# qube.net
KiCad netlist of a schematic drawn in EAGLE
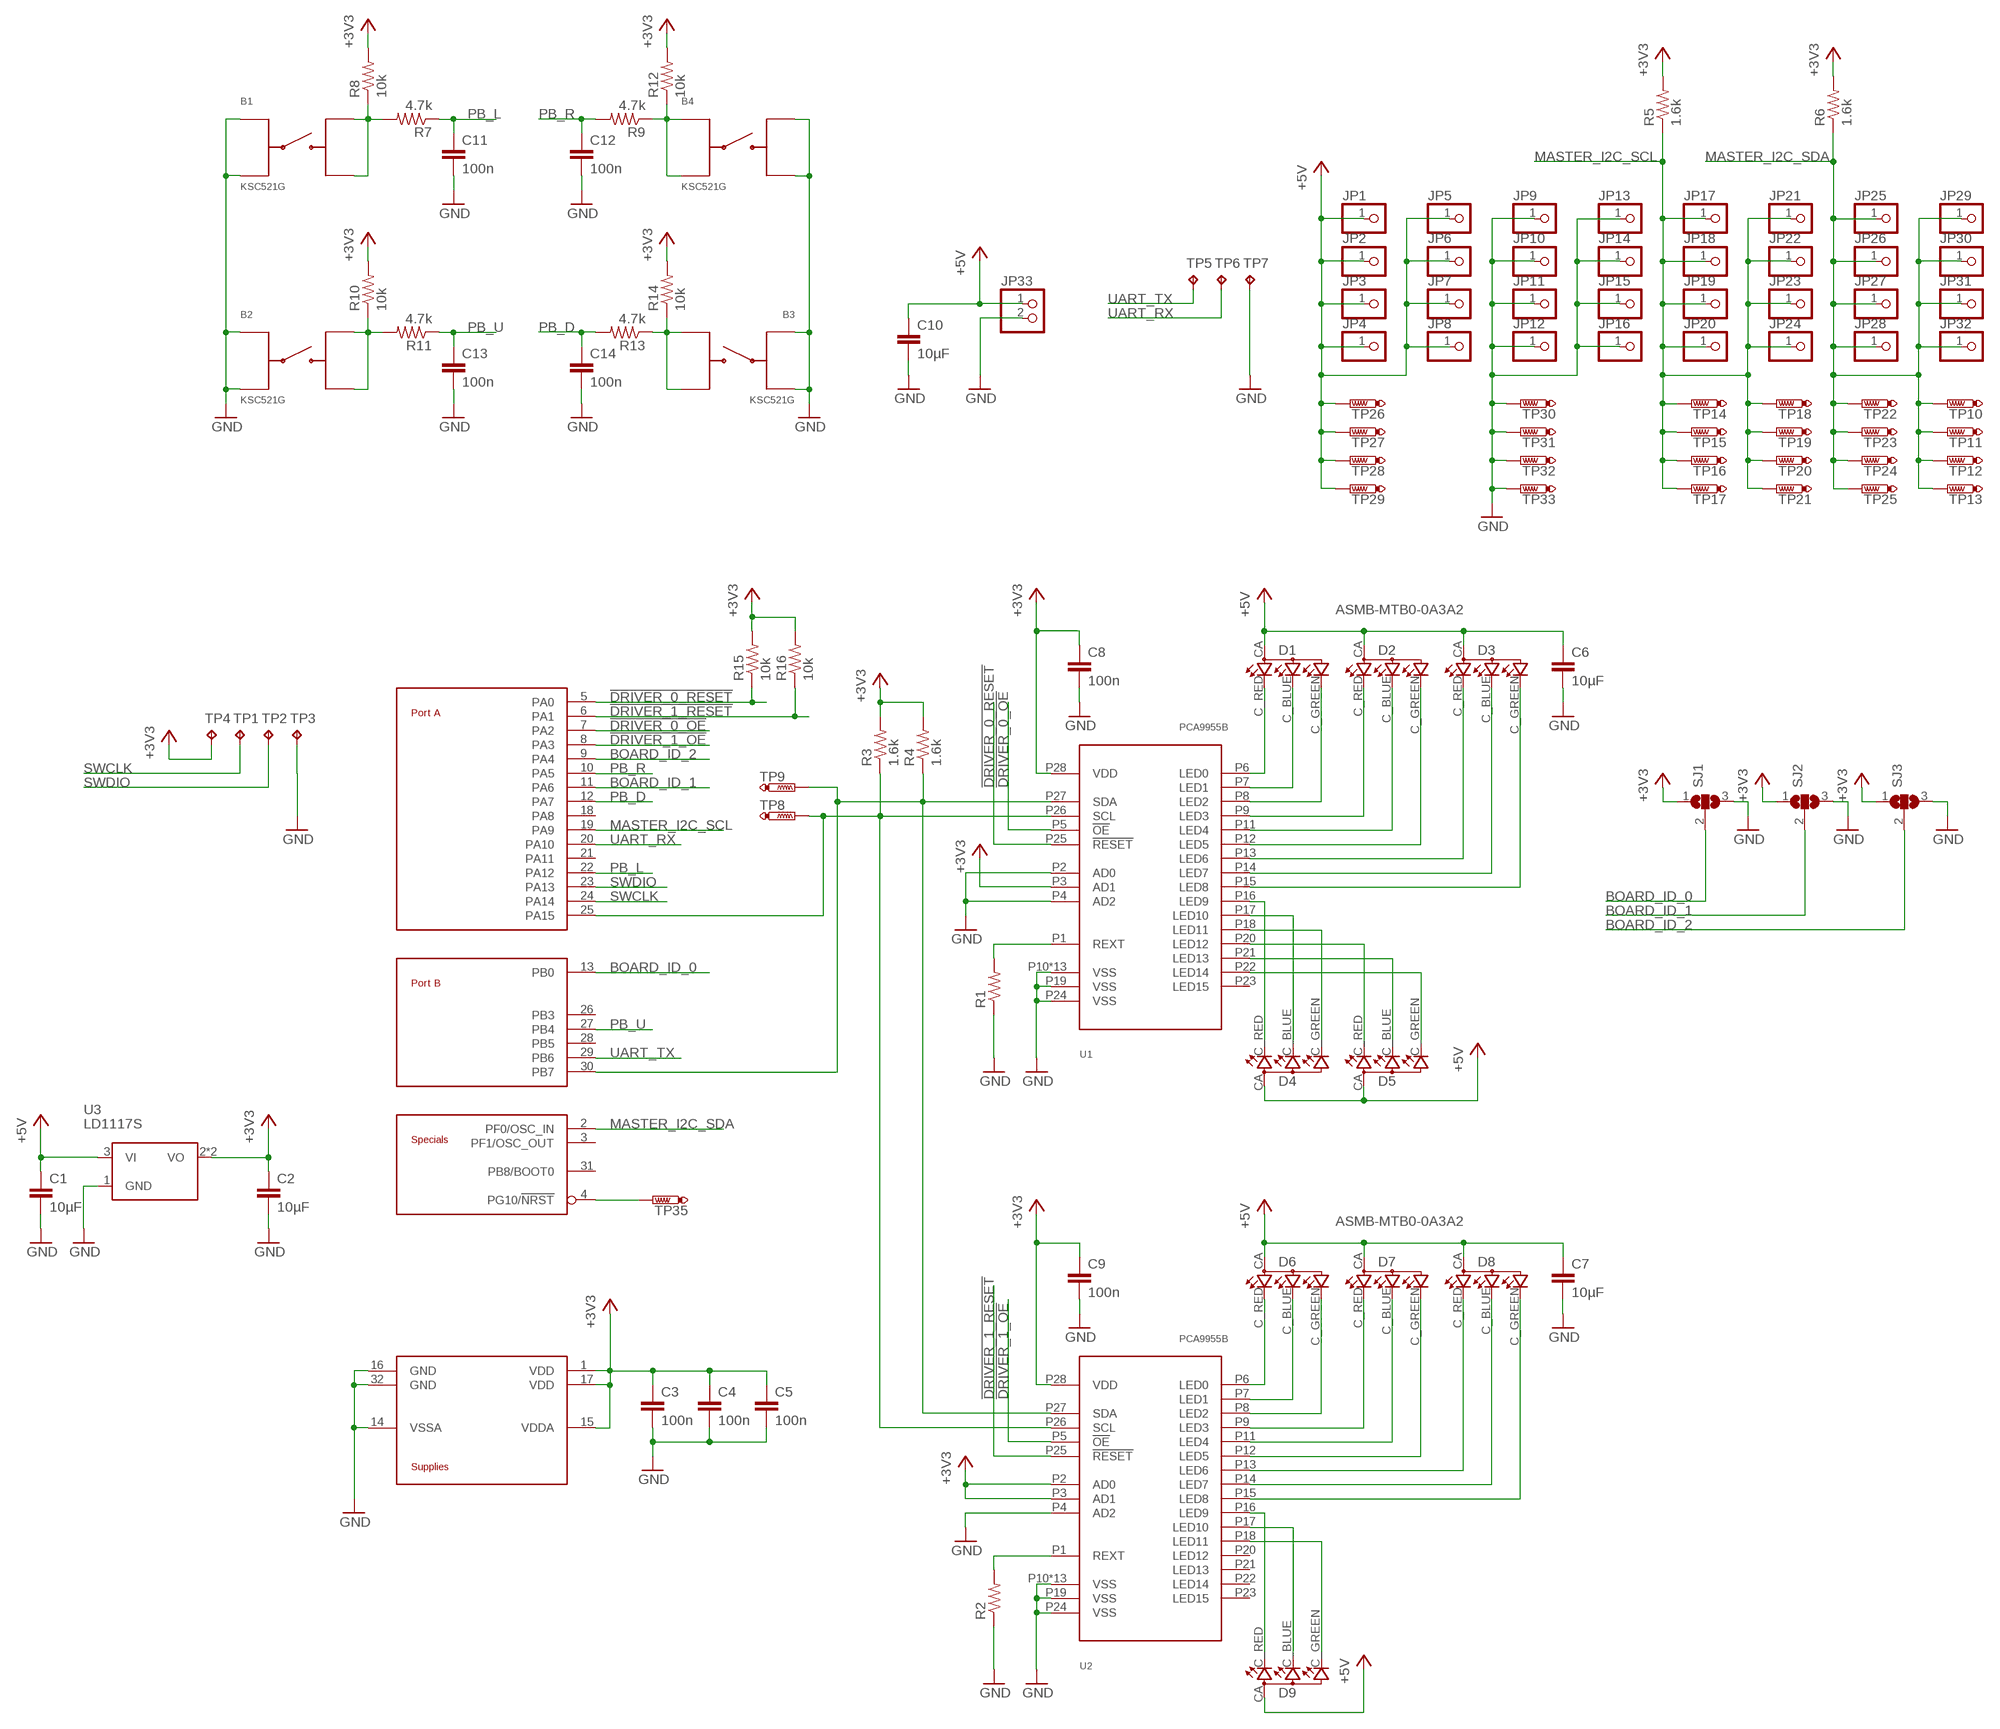
[diagram p0: schematic, sheet 1]

(export (version "E")
  (design (tool "Eeschema 10.0.6"))
  (components
    (comp (ref "B1")
      (value "KSC521G")
      (footprint "eagle-import:KSC521G")
      (libsource (lib "eagle-import") (part "KSC521G"))
    )
    (comp (ref "B2")
      (value "KSC521G")
      (footprint "eagle-import:KSC521G")
      (libsource (lib "eagle-import") (part "KSC521G"))
    )
    (comp (ref "B3")
      (value "KSC521G")
      (footprint "eagle-import:KSC521G")
      (libsource (lib "eagle-import") (part "KSC521G"))
    )
    (comp (ref "B4")
      (value "KSC521G")
      (footprint "eagle-import:KSC521G")
      (libsource (lib "eagle-import") (part "KSC521G"))
    )
    (comp (ref "C1")
      (value "10µF")
      (footprint "eagle-import:C0805")
      (libsource (lib "eagle-import") (part "C-EUC0805"))
    )
    (comp (ref "C2")
      (value "10µF")
      (footprint "eagle-import:C0805")
      (libsource (lib "eagle-import") (part "C-EUC0805"))
    )
    (comp (ref "C3")
      (value "100n")
      (footprint "eagle-import:C0805")
      (libsource (lib "eagle-import") (part "C-EUC0805"))
    )
    (comp (ref "C4")
      (value "100n")
      (footprint "eagle-import:C0805")
      (libsource (lib "eagle-import") (part "C-EUC0805"))
    )
    (comp (ref "C5")
      (value "100n")
      (footprint "eagle-import:C0805")
      (libsource (lib "eagle-import") (part "C-EUC0805"))
    )
    (comp (ref "C6")
      (value "10µF")
      (footprint "eagle-import:C0805")
      (libsource (lib "eagle-import") (part "C-EUC0805"))
    )
    (comp (ref "C7")
      (value "10µF")
      (footprint "eagle-import:C0805")
      (libsource (lib "eagle-import") (part "C-EUC0805"))
    )
    (comp (ref "C8")
      (value "100n")
      (footprint "eagle-import:C0805")
      (libsource (lib "eagle-import") (part "C-EUC0805"))
    )
    (comp (ref "C9")
      (value "100n")
      (footprint "eagle-import:C0805")
      (libsource (lib "eagle-import") (part "C-EUC0805"))
    )
    (comp (ref "C10")
      (value "10µF")
      (footprint "eagle-import:C0805")
      (libsource (lib "eagle-import") (part "C-EUC0805"))
    )
    (comp (ref "C11")
      (value "100n")
      (footprint "eagle-import:C0805")
      (libsource (lib "eagle-import") (part "C-EUC0805"))
    )
    (comp (ref "C12")
      (value "100n")
      (footprint "eagle-import:C0805")
      (libsource (lib "eagle-import") (part "C-EUC0805"))
    )
    (comp (ref "C13")
      (value "100n")
      (footprint "eagle-import:C0805")
      (libsource (lib "eagle-import") (part "C-EUC0805"))
    )
    (comp (ref "C14")
      (value "100n")
      (footprint "eagle-import:C0805")
      (libsource (lib "eagle-import") (part "C-EUC0805"))
    )
    (comp (ref "D1")
      (value "ASMB-MTB0-0A3A2")
      (footprint "eagle-import:PLCC-4")
      (libsource (lib "eagle-import") (part "ASMB-MTB0-0A3A2"))
    )
    (comp (ref "D2")
      (value "ASMB-MTB0-0A3A2")
      (footprint "eagle-import:PLCC-4")
      (libsource (lib "eagle-import") (part "ASMB-MTB0-0A3A2"))
    )
    (comp (ref "D3")
      (value "ASMB-MTB0-0A3A2")
      (footprint "eagle-import:PLCC-4")
      (libsource (lib "eagle-import") (part "ASMB-MTB0-0A3A2"))
    )
    (comp (ref "D4")
      (value "ASMB-MTB0-0A3A2")
      (footprint "eagle-import:PLCC-4")
      (libsource (lib "eagle-import") (part "ASMB-MTB0-0A3A2"))
    )
    (comp (ref "D5")
      (value "ASMB-MTB0-0A3A2")
      (footprint "eagle-import:PLCC-4")
      (libsource (lib "eagle-import") (part "ASMB-MTB0-0A3A2"))
    )
    (comp (ref "D6")
      (value "ASMB-MTB0-0A3A2")
      (footprint "eagle-import:PLCC-4")
      (libsource (lib "eagle-import") (part "ASMB-MTB0-0A3A2"))
    )
    (comp (ref "D7")
      (value "ASMB-MTB0-0A3A2")
      (footprint "eagle-import:PLCC-4")
      (libsource (lib "eagle-import") (part "ASMB-MTB0-0A3A2"))
    )
    (comp (ref "D8")
      (value "ASMB-MTB0-0A3A2")
      (footprint "eagle-import:PLCC-4")
      (libsource (lib "eagle-import") (part "ASMB-MTB0-0A3A2"))
    )
    (comp (ref "D9")
      (value "ASMB-MTB0-0A3A2")
      (footprint "eagle-import:PLCC-4")
      (libsource (lib "eagle-import") (part "ASMB-MTB0-0A3A2"))
    )
    (comp (ref "JP1")
      (value "PINHD-1X1")
      (footprint "eagle-import:1X01")
      (libsource (lib "eagle-import") (part "PINHD-1X1"))
    )
    (comp (ref "JP2")
      (value "PINHD-1X1")
      (footprint "eagle-import:1X01")
      (libsource (lib "eagle-import") (part "PINHD-1X1"))
    )
    (comp (ref "JP3")
      (value "PINHD-1X1")
      (footprint "eagle-import:1X01")
      (libsource (lib "eagle-import") (part "PINHD-1X1"))
    )
    (comp (ref "JP4")
      (value "PINHD-1X1")
      (footprint "eagle-import:1X01")
      (libsource (lib "eagle-import") (part "PINHD-1X1"))
    )
    (comp (ref "JP5")
      (value "PINHD-1X1")
      (footprint "eagle-import:1X01")
      (libsource (lib "eagle-import") (part "PINHD-1X1"))
    )
    (comp (ref "JP6")
      (value "PINHD-1X1")
      (footprint "eagle-import:1X01")
      (libsource (lib "eagle-import") (part "PINHD-1X1"))
    )
    (comp (ref "JP7")
      (value "PINHD-1X1")
      (footprint "eagle-import:1X01")
      (libsource (lib "eagle-import") (part "PINHD-1X1"))
    )
    (comp (ref "JP8")
      (value "PINHD-1X1")
      (footprint "eagle-import:1X01")
      (libsource (lib "eagle-import") (part "PINHD-1X1"))
    )
    (comp (ref "JP9")
      (value "PINHD-1X1")
      (footprint "eagle-import:1X01")
      (libsource (lib "eagle-import") (part "PINHD-1X1"))
    )
    (comp (ref "JP10")
      (value "PINHD-1X1")
      (footprint "eagle-import:1X01")
      (libsource (lib "eagle-import") (part "PINHD-1X1"))
    )
    (comp (ref "JP11")
      (value "PINHD-1X1")
      (footprint "eagle-import:1X01")
      (libsource (lib "eagle-import") (part "PINHD-1X1"))
    )
    (comp (ref "JP12")
      (value "PINHD-1X1")
      (footprint "eagle-import:1X01")
      (libsource (lib "eagle-import") (part "PINHD-1X1"))
    )
    (comp (ref "JP13")
      (value "PINHD-1X1")
      (footprint "eagle-import:1X01")
      (libsource (lib "eagle-import") (part "PINHD-1X1"))
    )
    (comp (ref "JP14")
      (value "PINHD-1X1")
      (footprint "eagle-import:1X01")
      (libsource (lib "eagle-import") (part "PINHD-1X1"))
    )
    (comp (ref "JP15")
      (value "PINHD-1X1")
      (footprint "eagle-import:1X01")
      (libsource (lib "eagle-import") (part "PINHD-1X1"))
    )
    (comp (ref "JP16")
      (value "PINHD-1X1")
      (footprint "eagle-import:1X01")
      (libsource (lib "eagle-import") (part "PINHD-1X1"))
    )
    (comp (ref "JP17")
      (value "PINHD-1X1")
      (footprint "eagle-import:1X01")
      (libsource (lib "eagle-import") (part "PINHD-1X1"))
    )
    (comp (ref "JP18")
      (value "PINHD-1X1")
      (footprint "eagle-import:1X01")
      (libsource (lib "eagle-import") (part "PINHD-1X1"))
    )
    (comp (ref "JP19")
      (value "PINHD-1X1")
      (footprint "eagle-import:1X01")
      (libsource (lib "eagle-import") (part "PINHD-1X1"))
    )
    (comp (ref "JP20")
      (value "PINHD-1X1")
      (footprint "eagle-import:1X01")
      (libsource (lib "eagle-import") (part "PINHD-1X1"))
    )
    (comp (ref "JP21")
      (value "PINHD-1X1")
      (footprint "eagle-import:1X01")
      (libsource (lib "eagle-import") (part "PINHD-1X1"))
    )
    (comp (ref "JP22")
      (value "PINHD-1X1")
      (footprint "eagle-import:1X01")
      (libsource (lib "eagle-import") (part "PINHD-1X1"))
    )
    (comp (ref "JP23")
      (value "PINHD-1X1")
      (footprint "eagle-import:1X01")
      (libsource (lib "eagle-import") (part "PINHD-1X1"))
    )
    (comp (ref "JP24")
      (value "PINHD-1X1")
      (footprint "eagle-import:1X01")
      (libsource (lib "eagle-import") (part "PINHD-1X1"))
    )
    (comp (ref "JP25")
      (value "PINHD-1X1")
      (footprint "eagle-import:1X01")
      (libsource (lib "eagle-import") (part "PINHD-1X1"))
    )
    (comp (ref "JP26")
      (value "PINHD-1X1")
      (footprint "eagle-import:1X01")
      (libsource (lib "eagle-import") (part "PINHD-1X1"))
    )
    (comp (ref "JP27")
      (value "PINHD-1X1")
      (footprint "eagle-import:1X01")
      (libsource (lib "eagle-import") (part "PINHD-1X1"))
    )
    (comp (ref "JP28")
      (value "PINHD-1X1")
      (footprint "eagle-import:1X01")
      (libsource (lib "eagle-import") (part "PINHD-1X1"))
    )
    (comp (ref "JP29")
      (value "PINHD-1X1")
      (footprint "eagle-import:1X01")
      (libsource (lib "eagle-import") (part "PINHD-1X1"))
    )
    (comp (ref "JP30")
      (value "PINHD-1X1")
      (footprint "eagle-import:1X01")
      (libsource (lib "eagle-import") (part "PINHD-1X1"))
    )
    (comp (ref "JP31")
      (value "PINHD-1X1")
      (footprint "eagle-import:1X01")
      (libsource (lib "eagle-import") (part "PINHD-1X1"))
    )
    (comp (ref "JP32")
      (value "PINHD-1X1")
      (footprint "eagle-import:1X01")
      (libsource (lib "eagle-import") (part "PINHD-1X1"))
    )
    (comp (ref "JP33")
      (value "PINHD-1X2/90")
      (footprint "eagle-import:1X02_90")
      (libsource (lib "eagle-import") (part "PINHD-1X2/90"))
    )
    (comp (ref "R1")
      (value "R-US_R0805")
      (footprint "eagle-import:R0805")
      (libsource (lib "eagle-import") (part "R-US_R0805"))
    )
    (comp (ref "R2")
      (value "R-US_R0805")
      (footprint "eagle-import:R0805")
      (libsource (lib "eagle-import") (part "R-US_R0805"))
    )
    (comp (ref "R3")
      (value "1.6k")
      (footprint "eagle-import:R0805")
      (libsource (lib "eagle-import") (part "R-US_R0805"))
    )
    (comp (ref "R4")
      (value "1.6k")
      (footprint "eagle-import:R0805")
      (libsource (lib "eagle-import") (part "R-US_R0805"))
    )
    (comp (ref "R5")
      (value "1.6k")
      (footprint "eagle-import:R0805")
      (libsource (lib "eagle-import") (part "R-US_R0805"))
    )
    (comp (ref "R6")
      (value "1.6k")
      (footprint "eagle-import:R0805")
      (libsource (lib "eagle-import") (part "R-US_R0805"))
    )
    (comp (ref "R7")
      (value "4.7k")
      (footprint "eagle-import:R0805")
      (libsource (lib "eagle-import") (part "R-US_R0805"))
    )
    (comp (ref "R8")
      (value "10k")
      (footprint "eagle-import:R0805")
      (libsource (lib "eagle-import") (part "R-US_R0805"))
    )
    (comp (ref "R9")
      (value "4.7k")
      (footprint "eagle-import:R0805")
      (libsource (lib "eagle-import") (part "R-US_R0805"))
    )
    (comp (ref "R10")
      (value "10k")
      (footprint "eagle-import:R0805")
      (libsource (lib "eagle-import") (part "R-US_R0805"))
    )
    (comp (ref "R11")
      (value "4.7k")
      (footprint "eagle-import:R0805")
      (libsource (lib "eagle-import") (part "R-US_R0805"))
    )
    (comp (ref "R12")
      (value "10k")
      (footprint "eagle-import:R0805")
      (libsource (lib "eagle-import") (part "R-US_R0805"))
    )
    (comp (ref "R13")
      (value "4.7k")
      (footprint "eagle-import:R0805")
      (libsource (lib "eagle-import") (part "R-US_R0805"))
    )
    (comp (ref "R14")
      (value "10k")
      (footprint "eagle-import:R0805")
      (libsource (lib "eagle-import") (part "R-US_R0805"))
    )
    (comp (ref "R15")
      (value "10k")
      (footprint "eagle-import:R0805")
      (libsource (lib "eagle-import") (part "R-US_R0805"))
    )
    (comp (ref "R16")
      (value "10k")
      (footprint "eagle-import:R0805")
      (libsource (lib "eagle-import") (part "R-US_R0805"))
    )
    (comp (ref "SJ1")
      (value "SJ2W")
      (footprint "eagle-import:SJ_2")
      (libsource (lib "eagle-import") (part "SJ2W"))
    )
    (comp (ref "SJ2")
      (value "SJ2W")
      (footprint "eagle-import:SJ_2")
      (libsource (lib "eagle-import") (part "SJ2W"))
    )
    (comp (ref "SJ3")
      (value "SJ2W")
      (footprint "eagle-import:SJ_2")
      (libsource (lib "eagle-import") (part "SJ2W"))
    )
    (comp (ref "TP1")
      (value "TPTP18R")
      (footprint "eagle-import:TP18R")
      (libsource (lib "eagle-import") (part "TPTP18R"))
    )
    (comp (ref "TP2")
      (value "TPTP18R")
      (footprint "eagle-import:TP18R")
      (libsource (lib "eagle-import") (part "TPTP18R"))
    )
    (comp (ref "TP3")
      (value "TPTP18R")
      (footprint "eagle-import:TP18R")
      (libsource (lib "eagle-import") (part "TPTP18R"))
    )
    (comp (ref "TP4")
      (value "TPTP18R")
      (footprint "eagle-import:TP18R")
      (libsource (lib "eagle-import") (part "TPTP18R"))
    )
    (comp (ref "TP5")
      (value "TPTP18R")
      (footprint "eagle-import:TP18R")
      (libsource (lib "eagle-import") (part "TPTP18R"))
    )
    (comp (ref "TP6")
      (value "TPTP18R")
      (footprint "eagle-import:TP18R")
      (libsource (lib "eagle-import") (part "TPTP18R"))
    )
    (comp (ref "TP7")
      (value "TPTP18R")
      (footprint "eagle-import:TP18R")
      (libsource (lib "eagle-import") (part "TPTP18R"))
    )
    (comp (ref "TP8")
      (value "PTR1TP15SQ")
      (footprint "eagle-import:TP15SQ")
      (libsource (lib "eagle-import") (part "PTR1TP15SQ"))
    )
    (comp (ref "TP9")
      (value "PTR1TP15SQ")
      (footprint "eagle-import:TP15SQ")
      (libsource (lib "eagle-import") (part "PTR1TP15SQ"))
    )
    (comp (ref "TP10")
      (value "PTR1TP15SQ")
      (footprint "eagle-import:TP15SQ")
      (libsource (lib "eagle-import") (part "PTR1TP15SQ"))
    )
    (comp (ref "TP11")
      (value "PTR1TP15SQ")
      (footprint "eagle-import:TP15SQ")
      (libsource (lib "eagle-import") (part "PTR1TP15SQ"))
    )
    (comp (ref "TP12")
      (value "PTR1TP15SQ")
      (footprint "eagle-import:TP15SQ")
      (libsource (lib "eagle-import") (part "PTR1TP15SQ"))
    )
    (comp (ref "TP13")
      (value "PTR1TP15SQ")
      (footprint "eagle-import:TP15SQ")
      (libsource (lib "eagle-import") (part "PTR1TP15SQ"))
    )
    (comp (ref "TP14")
      (value "PTR1TP15SQ")
      (footprint "eagle-import:TP15SQ")
      (libsource (lib "eagle-import") (part "PTR1TP15SQ"))
    )
    (comp (ref "TP15")
      (value "PTR1TP15SQ")
      (footprint "eagle-import:TP15SQ")
      (libsource (lib "eagle-import") (part "PTR1TP15SQ"))
    )
    (comp (ref "TP16")
      (value "PTR1TP15SQ")
      (footprint "eagle-import:TP15SQ")
      (libsource (lib "eagle-import") (part "PTR1TP15SQ"))
    )
    (comp (ref "TP17")
      (value "PTR1TP15SQ")
      (footprint "eagle-import:TP15SQ")
      (libsource (lib "eagle-import") (part "PTR1TP15SQ"))
    )
    (comp (ref "TP18")
      (value "PTR1TP15SQ")
      (footprint "eagle-import:TP15SQ")
      (libsource (lib "eagle-import") (part "PTR1TP15SQ"))
    )
    (comp (ref "TP19")
      (value "PTR1TP15SQ")
      (footprint "eagle-import:TP15SQ")
      (libsource (lib "eagle-import") (part "PTR1TP15SQ"))
    )
    (comp (ref "TP20")
      (value "PTR1TP15SQ")
      (footprint "eagle-import:TP15SQ")
      (libsource (lib "eagle-import") (part "PTR1TP15SQ"))
    )
    (comp (ref "TP21")
      (value "PTR1TP15SQ")
      (footprint "eagle-import:TP15SQ")
      (libsource (lib "eagle-import") (part "PTR1TP15SQ"))
    )
    (comp (ref "TP22")
      (value "PTR1TP15SQ")
      (footprint "eagle-import:TP15SQ")
      (libsource (lib "eagle-import") (part "PTR1TP15SQ"))
    )
    (comp (ref "TP23")
      (value "PTR1TP15SQ")
      (footprint "eagle-import:TP15SQ")
      (libsource (lib "eagle-import") (part "PTR1TP15SQ"))
    )
    (comp (ref "TP24")
      (value "PTR1TP15SQ")
      (footprint "eagle-import:TP15SQ")
      (libsource (lib "eagle-import") (part "PTR1TP15SQ"))
    )
    (comp (ref "TP25")
      (value "PTR1TP15SQ")
      (footprint "eagle-import:TP15SQ")
      (libsource (lib "eagle-import") (part "PTR1TP15SQ"))
    )
    (comp (ref "TP26")
      (value "PTR1TP15SQ")
      (footprint "eagle-import:TP15SQ")
      (libsource (lib "eagle-import") (part "PTR1TP15SQ"))
    )
    (comp (ref "TP27")
      (value "PTR1TP15SQ")
      (footprint "eagle-import:TP15SQ")
      (libsource (lib "eagle-import") (part "PTR1TP15SQ"))
    )
    (comp (ref "TP28")
      (value "PTR1TP15SQ")
      (footprint "eagle-import:TP15SQ")
      (libsource (lib "eagle-import") (part "PTR1TP15SQ"))
    )
    (comp (ref "TP29")
      (value "PTR1TP15SQ")
      (footprint "eagle-import:TP15SQ")
      (libsource (lib "eagle-import") (part "PTR1TP15SQ"))
    )
    (comp (ref "TP30")
      (value "PTR1TP15SQ")
      (footprint "eagle-import:TP15SQ")
      (libsource (lib "eagle-import") (part "PTR1TP15SQ"))
    )
    (comp (ref "TP31")
      (value "PTR1TP15SQ")
      (footprint "eagle-import:TP15SQ")
      (libsource (lib "eagle-import") (part "PTR1TP15SQ"))
    )
    (comp (ref "TP32")
      (value "PTR1TP15SQ")
      (footprint "eagle-import:TP15SQ")
      (libsource (lib "eagle-import") (part "PTR1TP15SQ"))
    )
    (comp (ref "TP33")
      (value "PTR1TP15SQ")
      (footprint "eagle-import:TP15SQ")
      (libsource (lib "eagle-import") (part "PTR1TP15SQ"))
    )
    (comp (ref "TP35")
      (value "PTR1TP10R")
      (footprint "eagle-import:TP10R")
      (libsource (lib "eagle-import") (part "PTR1TP10R"))
    )
    (comp (ref "U$1")
      (value "STM32G431KB")
      (footprint "eagle-import:LQFP32")
      (libsource (lib "eagle-import") (part "STM32G431KB"))
    )
    (comp (ref "U1")
      (value "PCA9955B")
      (footprint "eagle-import:HTSSOP28")
      (libsource (lib "eagle-import") (part "PCA9955B"))
    )
    (comp (ref "U2")
      (value "PCA9955B")
      (footprint "eagle-import:HTSSOP28")
      (libsource (lib "eagle-import") (part "PCA9955B"))
    )
    (comp (ref "U3")
      (value "LD1117S")
      (footprint "eagle-import:SOT223")
      (libsource (lib "eagle-import") (part "LD1117S"))
    )
  )
  (nets
    (net (code "1") (name "+3V3") (class "Default")
      (node (ref "C2") (pin "1") (pinfunction "1_1") (pintype "passive"))
      (node (ref "C3") (pin "1") (pinfunction "1_1") (pintype "passive"))
      (node (ref "C4") (pin "1") (pinfunction "1_1") (pintype "passive"))
      (node (ref "C5") (pin "1") (pinfunction "1_1") (pintype "passive"))
      (node (ref "C8") (pin "1") (pinfunction "1_1") (pintype "passive"))
      (node (ref "C9") (pin "1") (pinfunction "1_1") (pintype "passive"))
      (node (ref "R10") (pin "2") (pinfunction "2_2") (pintype "passive"))
      (node (ref "R12") (pin "2") (pinfunction "2_2") (pintype "passive"))
      (node (ref "R14") (pin "2") (pinfunction "2_2") (pintype "passive"))
      (node (ref "R15") (pin "2") (pinfunction "2_2") (pintype "passive"))
      (node (ref "R16") (pin "2") (pinfunction "2_2") (pintype "passive"))
      (node (ref "R3") (pin "2") (pinfunction "2_2") (pintype "passive"))
      (node (ref "R4") (pin "2") (pinfunction "2_2") (pintype "passive"))
      (node (ref "R5") (pin "2") (pinfunction "2_2") (pintype "passive"))
      (node (ref "R6") (pin "2") (pinfunction "2_2") (pintype "passive"))
      (node (ref "R8") (pin "2") (pinfunction "2_2") (pintype "passive"))
      (node (ref "SJ1") (pin "1") (pinfunction "1_1") (pintype "passive"))
      (node (ref "SJ2") (pin "1") (pinfunction "1_1") (pintype "passive"))
      (node (ref "SJ3") (pin "1") (pinfunction "1_1") (pintype "passive"))
      (node (ref "TP4") (pin "TP") (pinfunction "TP_TP") (pintype "input"))
      (node (ref "U$1") (pin "1") (pinfunction "VDD_1") (pintype "power_in"))
      (node (ref "U$1") (pin "15") (pinfunction "VDDA_15") (pintype "power_in"))
      (node (ref "U$1") (pin "17") (pinfunction "VDD_17") (pintype "power_in"))
      (node (ref "U1") (pin "P28") (pinfunction "VDD_P28") (pintype "power_in"))
      (node (ref "U1") (pin "P3") (pinfunction "AD1_P3") (pintype "input"))
      (node (ref "U2") (pin "P2") (pinfunction "AD0_P2") (pintype "input"))
      (node (ref "U2") (pin "P28") (pinfunction "VDD_P28") (pintype "power_in"))
      (node (ref "U2") (pin "P3") (pinfunction "AD1_P3") (pintype "input"))
      (node (ref "U3") (pin "2") (pinfunction "VO_2") (pintype "power_in"))
      (node (ref "U3") (pin "4") (pinfunction "VO_4") (pintype "power_in"))
    )
    (net (code "2") (name "+5V") (class "Default")
      (node (ref "C1") (pin "1") (pinfunction "1_1") (pintype "passive"))
      (node (ref "C10") (pin "1") (pinfunction "1_1") (pintype "passive"))
      (node (ref "C6") (pin "1") (pinfunction "1_1") (pintype "passive"))
      (node (ref "C7") (pin "1") (pinfunction "1_1") (pintype "passive"))
      (node (ref "D1") (pin "CA") (pinfunction "A2_CA") (pintype "passive"))
      (node (ref "D2") (pin "CA") (pinfunction "A2_CA") (pintype "passive"))
      (node (ref "D3") (pin "CA") (pinfunction "A2_CA") (pintype "passive"))
      (node (ref "D4") (pin "CA") (pinfunction "A2_CA") (pintype "passive"))
      (node (ref "D5") (pin "CA") (pinfunction "A2_CA") (pintype "passive"))
      (node (ref "D6") (pin "CA") (pinfunction "A2_CA") (pintype "passive"))
      (node (ref "D7") (pin "CA") (pinfunction "A2_CA") (pintype "passive"))
      (node (ref "D8") (pin "CA") (pinfunction "A2_CA") (pintype "passive"))
      (node (ref "D9") (pin "CA") (pinfunction "A2_CA") (pintype "passive"))
      (node (ref "JP1") (pin "1") (pinfunction "1_1") (pintype "passive"))
      (node (ref "JP2") (pin "1") (pinfunction "1_1") (pintype "passive"))
      (node (ref "JP3") (pin "1") (pinfunction "1_1") (pintype "passive"))
      (node (ref "JP33") (pin "1") (pinfunction "1_1") (pintype "passive"))
      (node (ref "JP4") (pin "1") (pinfunction "1_1") (pintype "passive"))
      (node (ref "JP5") (pin "1") (pinfunction "1_1") (pintype "passive"))
      (node (ref "JP6") (pin "1") (pinfunction "1_1") (pintype "passive"))
      (node (ref "JP7") (pin "1") (pinfunction "1_1") (pintype "passive"))
      (node (ref "JP8") (pin "1") (pinfunction "1_1") (pintype "passive"))
      (node (ref "TP26") (pin "TP") (pinfunction "TP_TP") (pintype "input"))
      (node (ref "TP27") (pin "TP") (pinfunction "TP_TP") (pintype "input"))
      (node (ref "TP28") (pin "TP") (pinfunction "TP_TP") (pintype "input"))
      (node (ref "TP29") (pin "TP") (pinfunction "TP_TP") (pintype "input"))
      (node (ref "U3") (pin "3") (pinfunction "VI_3") (pintype "power_in"))
    )
    (net (code "3") (name "/BOARD_ID_0") (class "Default")
      (node (ref "SJ1") (pin "2") (pinfunction "2_2") (pintype "passive"))
      (node (ref "U$1") (pin "13") (pinfunction "PB0_13") (pintype "bidirectional"))
    )
    (net (code "4") (name "/BOARD_ID_1") (class "Default")
      (node (ref "SJ2") (pin "2") (pinfunction "2_2") (pintype "passive"))
      (node (ref "U$1") (pin "11") (pinfunction "PA6_11") (pintype "bidirectional"))
    )
    (net (code "5") (name "/BOARD_ID_2") (class "Default")
      (node (ref "SJ3") (pin "2") (pinfunction "2_2") (pintype "passive"))
      (node (ref "U$1") (pin "9") (pinfunction "PA4_9") (pintype "bidirectional"))
    )
    (net (code "6") (name "/MASTER_I2C_SCL") (class "Default")
      (node (ref "JP17") (pin "1") (pinfunction "1_1") (pintype "passive"))
      (node (ref "JP18") (pin "1") (pinfunction "1_1") (pintype "passive"))
      (node (ref "JP19") (pin "1") (pinfunction "1_1") (pintype "passive"))
      (node (ref "JP20") (pin "1") (pinfunction "1_1") (pintype "passive"))
      (node (ref "JP21") (pin "1") (pinfunction "1_1") (pintype "passive"))
      (node (ref "JP22") (pin "1") (pinfunction "1_1") (pintype "passive"))
      (node (ref "JP23") (pin "1") (pinfunction "1_1") (pintype "passive"))
      (node (ref "JP24") (pin "1") (pinfunction "1_1") (pintype "passive"))
      (node (ref "R5") (pin "1") (pinfunction "1_1") (pintype "passive"))
      (node (ref "TP14") (pin "TP") (pinfunction "TP_TP") (pintype "input"))
      (node (ref "TP15") (pin "TP") (pinfunction "TP_TP") (pintype "input"))
      (node (ref "TP16") (pin "TP") (pinfunction "TP_TP") (pintype "input"))
      (node (ref "TP17") (pin "TP") (pinfunction "TP_TP") (pintype "input"))
      (node (ref "TP18") (pin "TP") (pinfunction "TP_TP") (pintype "input"))
      (node (ref "TP19") (pin "TP") (pinfunction "TP_TP") (pintype "input"))
      (node (ref "TP20") (pin "TP") (pinfunction "TP_TP") (pintype "input"))
      (node (ref "TP21") (pin "TP") (pinfunction "TP_TP") (pintype "input"))
      (node (ref "U$1") (pin "19") (pinfunction "PA9_19") (pintype "bidirectional"))
    )
    (net (code "7") (name "/MASTER_I2C_SDA") (class "Default")
      (node (ref "JP25") (pin "1") (pinfunction "1_1") (pintype "passive"))
      (node (ref "JP26") (pin "1") (pinfunction "1_1") (pintype "passive"))
      (node (ref "JP27") (pin "1") (pinfunction "1_1") (pintype "passive"))
      (node (ref "JP28") (pin "1") (pinfunction "1_1") (pintype "passive"))
      (node (ref "JP29") (pin "1") (pinfunction "1_1") (pintype "passive"))
      (node (ref "JP30") (pin "1") (pinfunction "1_1") (pintype "passive"))
      (node (ref "JP31") (pin "1") (pinfunction "1_1") (pintype "passive"))
      (node (ref "JP32") (pin "1") (pinfunction "1_1") (pintype "passive"))
      (node (ref "R6") (pin "1") (pinfunction "1_1") (pintype "passive"))
      (node (ref "TP10") (pin "TP") (pinfunction "TP_TP") (pintype "input"))
      (node (ref "TP11") (pin "TP") (pinfunction "TP_TP") (pintype "input"))
      (node (ref "TP12") (pin "TP") (pinfunction "TP_TP") (pintype "input"))
      (node (ref "TP13") (pin "TP") (pinfunction "TP_TP") (pintype "input"))
      (node (ref "TP22") (pin "TP") (pinfunction "TP_TP") (pintype "input"))
      (node (ref "TP23") (pin "TP") (pinfunction "TP_TP") (pintype "input"))
      (node (ref "TP24") (pin "TP") (pinfunction "TP_TP") (pintype "input"))
      (node (ref "TP25") (pin "TP") (pinfunction "TP_TP") (pintype "input"))
      (node (ref "U$1") (pin "2") (pinfunction "PF0/OSC_IN_2") (pintype "input"))
    )
    (net (code "8") (name "/PB_D") (class "Default")
      (node (ref "C14") (pin "1") (pinfunction "1_1") (pintype "passive"))
      (node (ref "R13") (pin "2") (pinfunction "2_2") (pintype "passive"))
      (node (ref "U$1") (pin "12") (pinfunction "PA7_12") (pintype "bidirectional"))
    )
    (net (code "9") (name "/PB_L") (class "Default")
      (node (ref "C11") (pin "1") (pinfunction "1_1") (pintype "passive"))
      (node (ref "R7") (pin "1") (pinfunction "1_1") (pintype "passive"))
      (node (ref "U$1") (pin "22") (pinfunction "PA12_22") (pintype "bidirectional"))
    )
    (net (code "10") (name "/PB_R") (class "Default")
      (node (ref "C12") (pin "1") (pinfunction "1_1") (pintype "passive"))
      (node (ref "R9") (pin "2") (pinfunction "2_2") (pintype "passive"))
      (node (ref "U$1") (pin "10") (pinfunction "PA5_10") (pintype "bidirectional"))
    )
    (net (code "11") (name "/PB_U") (class "Default")
      (node (ref "C13") (pin "1") (pinfunction "1_1") (pintype "passive"))
      (node (ref "R11") (pin "1") (pinfunction "1_1") (pintype "passive"))
      (node (ref "U$1") (pin "27") (pinfunction "PB4_27") (pintype "bidirectional"))
    )
    (net (code "12") (name "/SWCLK") (class "Default")
      (node (ref "TP1") (pin "TP") (pinfunction "TP_TP") (pintype "input"))
      (node (ref "U$1") (pin "24") (pinfunction "PA14_24") (pintype "bidirectional"))
    )
    (net (code "13") (name "/SWDIO") (class "Default")
      (node (ref "TP2") (pin "TP") (pinfunction "TP_TP") (pintype "input"))
      (node (ref "U$1") (pin "23") (pinfunction "PA13_23") (pintype "bidirectional"))
    )
    (net (code "14") (name "/UART_RX") (class "Default")
      (node (ref "TP6") (pin "TP") (pinfunction "TP_TP") (pintype "input"))
      (node (ref "U$1") (pin "20") (pinfunction "PA10_20") (pintype "bidirectional"))
    )
    (net (code "15") (name "/UART_TX") (class "Default")
      (node (ref "TP5") (pin "TP") (pinfunction "TP_TP") (pintype "input"))
      (node (ref "U$1") (pin "29") (pinfunction "PB6_29") (pintype "bidirectional"))
    )
    (net (code "16") (name "/~{DRIVER_0_OE}") (class "Default")
      (node (ref "U$1") (pin "7") (pinfunction "PA2_7") (pintype "bidirectional"))
      (node (ref "U1") (pin "P5") (pinfunction "~{OE}_P5") (pintype "input"))
    )
    (net (code "17") (name "/~{DRIVER_0_RESET}") (class "Default")
      (node (ref "R15") (pin "1") (pinfunction "1_1") (pintype "passive"))
      (node (ref "U$1") (pin "5") (pinfunction "PA0_5") (pintype "bidirectional"))
      (node (ref "U1") (pin "P25") (pinfunction "~{RESET}_P25") (pintype "input"))
    )
    (net (code "18") (name "/~{DRIVER_1_OE}") (class "Default")
      (node (ref "U$1") (pin "8") (pinfunction "PA3_8") (pintype "bidirectional"))
      (node (ref "U2") (pin "P5") (pinfunction "~{OE}_P5") (pintype "input"))
    )
    (net (code "19") (name "/~{DRIVER_1_RESET}") (class "Default")
      (node (ref "R16") (pin "1") (pinfunction "1_1") (pintype "passive"))
      (node (ref "U$1") (pin "6") (pinfunction "PA1_6") (pintype "bidirectional"))
      (node (ref "U2") (pin "P25") (pinfunction "~{RESET}_P25") (pintype "input"))
    )
    (net (code "20") (name "GND") (class "Default")
      (node (ref "B1") (pin "3") (pinfunction "3_3") (pintype "bidirectional"))
      (node (ref "B1") (pin "4") (pinfunction "4_4") (pintype "bidirectional"))
      (node (ref "B2") (pin "3") (pinfunction "3_3") (pintype "bidirectional"))
      (node (ref "B2") (pin "4") (pinfunction "4_4") (pintype "bidirectional"))
      (node (ref "B3") (pin "3") (pinfunction "3_3") (pintype "bidirectional"))
      (node (ref "B3") (pin "4") (pinfunction "4_4") (pintype "bidirectional"))
      (node (ref "B4") (pin "1") (pinfunction "1_1") (pintype "bidirectional"))
      (node (ref "B4") (pin "2") (pinfunction "2_2") (pintype "bidirectional"))
      (node (ref "C1") (pin "2") (pinfunction "2_2") (pintype "passive"))
      (node (ref "C10") (pin "2") (pinfunction "2_2") (pintype "passive"))
      (node (ref "C11") (pin "2") (pinfunction "2_2") (pintype "passive"))
      (node (ref "C12") (pin "2") (pinfunction "2_2") (pintype "passive"))
      (node (ref "C13") (pin "2") (pinfunction "2_2") (pintype "passive"))
      (node (ref "C14") (pin "2") (pinfunction "2_2") (pintype "passive"))
      (node (ref "C2") (pin "2") (pinfunction "2_2") (pintype "passive"))
      (node (ref "C3") (pin "2") (pinfunction "2_2") (pintype "passive"))
      (node (ref "C4") (pin "2") (pinfunction "2_2") (pintype "passive"))
      (node (ref "C5") (pin "2") (pinfunction "2_2") (pintype "passive"))
      (node (ref "C6") (pin "2") (pinfunction "2_2") (pintype "passive"))
      (node (ref "C7") (pin "2") (pinfunction "2_2") (pintype "passive"))
      (node (ref "C8") (pin "2") (pinfunction "2_2") (pintype "passive"))
      (node (ref "C9") (pin "2") (pinfunction "2_2") (pintype "passive"))
      (node (ref "JP10") (pin "1") (pinfunction "1_1") (pintype "passive"))
      (node (ref "JP11") (pin "1") (pinfunction "1_1") (pintype "passive"))
      (node (ref "JP12") (pin "1") (pinfunction "1_1") (pintype "passive"))
      (node (ref "JP13") (pin "1") (pinfunction "1_1") (pintype "passive"))
      (node (ref "JP14") (pin "1") (pinfunction "1_1") (pintype "passive"))
      (node (ref "JP15") (pin "1") (pinfunction "1_1") (pintype "passive"))
      (node (ref "JP16") (pin "1") (pinfunction "1_1") (pintype "passive"))
      (node (ref "JP33") (pin "2") (pinfunction "2_2") (pintype "passive"))
      (node (ref "JP9") (pin "1") (pinfunction "1_1") (pintype "passive"))
      (node (ref "R1") (pin "1") (pinfunction "1_1") (pintype "passive"))
      (node (ref "R2") (pin "1") (pinfunction "1_1") (pintype "passive"))
      (node (ref "SJ1") (pin "3") (pinfunction "3_3") (pintype "passive"))
      (node (ref "SJ2") (pin "3") (pinfunction "3_3") (pintype "passive"))
      (node (ref "SJ3") (pin "3") (pinfunction "3_3") (pintype "passive"))
      (node (ref "TP3") (pin "TP") (pinfunction "TP_TP") (pintype "input"))
      (node (ref "TP30") (pin "TP") (pinfunction "TP_TP") (pintype "input"))
      (node (ref "TP31") (pin "TP") (pinfunction "TP_TP") (pintype "input"))
      (node (ref "TP32") (pin "TP") (pinfunction "TP_TP") (pintype "input"))
      (node (ref "TP33") (pin "TP") (pinfunction "TP_TP") (pintype "input"))
      (node (ref "TP7") (pin "TP") (pinfunction "TP_TP") (pintype "input"))
      (node (ref "U$1") (pin "14") (pinfunction "VSSA_14") (pintype "power_in"))
      (node (ref "U$1") (pin "16") (pinfunction "GND_16") (pintype "power_in"))
      (node (ref "U$1") (pin "32") (pinfunction "GND_32") (pintype "power_in"))
      (node (ref "U1") (pin "P10") (pinfunction "VSS_P10") (pintype "power_in"))
      (node (ref "U1") (pin "P19") (pinfunction "VSS_P19") (pintype "power_in"))
      (node (ref "U1") (pin "P2") (pinfunction "AD0_P2") (pintype "input"))
      (node (ref "U1") (pin "P24") (pinfunction "VSS_P24") (pintype "power_in"))
      (node (ref "U1") (pin "P4") (pinfunction "AD2_P4") (pintype "input"))
      (node (ref "U1") (pin "PWR_PAD1") (pinfunction "VSS_PWR_PAD1") (pintype "power_in"))
      (node (ref "U1") (pin "PWR_PAD10") (pinfunction "VSS_PWR_PAD10") (pintype "power_in"))
      (node (ref "U1") (pin "PWR_PAD11") (pinfunction "VSS_PWR_PAD11") (pintype "power_in"))
      (node (ref "U1") (pin "PWR_PAD12") (pinfunction "VSS_PWR_PAD12") (pintype "power_in"))
      (node (ref "U1") (pin "PWR_PAD2") (pinfunction "VSS_PWR_PAD2") (pintype "power_in"))
      (node (ref "U1") (pin "PWR_PAD3") (pinfunction "VSS_PWR_PAD3") (pintype "power_in"))
      (node (ref "U1") (pin "PWR_PAD4") (pinfunction "VSS_PWR_PAD4") (pintype "power_in"))
      (node (ref "U1") (pin "PWR_PAD5") (pinfunction "VSS_PWR_PAD5") (pintype "power_in"))
      (node (ref "U1") (pin "PWR_PAD6") (pinfunction "VSS_PWR_PAD6") (pintype "power_in"))
      (node (ref "U1") (pin "PWR_PAD7") (pinfunction "VSS_PWR_PAD7") (pintype "power_in"))
      (node (ref "U1") (pin "PWR_PAD8") (pinfunction "VSS_PWR_PAD8") (pintype "power_in"))
      (node (ref "U1") (pin "PWR_PAD9") (pinfunction "VSS_PWR_PAD9") (pintype "power_in"))
      (node (ref "U2") (pin "P10") (pinfunction "VSS_P10") (pintype "power_in"))
      (node (ref "U2") (pin "P19") (pinfunction "VSS_P19") (pintype "power_in"))
      (node (ref "U2") (pin "P24") (pinfunction "VSS_P24") (pintype "power_in"))
      (node (ref "U2") (pin "P4") (pinfunction "AD2_P4") (pintype "input"))
      (node (ref "U2") (pin "PWR_PAD1") (pinfunction "VSS_PWR_PAD1") (pintype "power_in"))
      (node (ref "U2") (pin "PWR_PAD10") (pinfunction "VSS_PWR_PAD10") (pintype "power_in"))
      (node (ref "U2") (pin "PWR_PAD11") (pinfunction "VSS_PWR_PAD11") (pintype "power_in"))
      (node (ref "U2") (pin "PWR_PAD12") (pinfunction "VSS_PWR_PAD12") (pintype "power_in"))
      (node (ref "U2") (pin "PWR_PAD2") (pinfunction "VSS_PWR_PAD2") (pintype "power_in"))
      (node (ref "U2") (pin "PWR_PAD3") (pinfunction "VSS_PWR_PAD3") (pintype "power_in"))
      (node (ref "U2") (pin "PWR_PAD4") (pinfunction "VSS_PWR_PAD4") (pintype "power_in"))
      (node (ref "U2") (pin "PWR_PAD5") (pinfunction "VSS_PWR_PAD5") (pintype "power_in"))
      (node (ref "U2") (pin "PWR_PAD6") (pinfunction "VSS_PWR_PAD6") (pintype "power_in"))
      (node (ref "U2") (pin "PWR_PAD7") (pinfunction "VSS_PWR_PAD7") (pintype "power_in"))
      (node (ref "U2") (pin "PWR_PAD8") (pinfunction "VSS_PWR_PAD8") (pintype "power_in"))
      (node (ref "U2") (pin "PWR_PAD9") (pinfunction "VSS_PWR_PAD9") (pintype "power_in"))
      (node (ref "U3") (pin "1") (pinfunction "GND_1") (pintype "power_in"))
    )
    (net (code "21") (name "Net-(B1-Pad1)") (class "Default")
      (node (ref "B1") (pin "1") (pinfunction "1_1") (pintype "bidirectional"))
      (node (ref "B1") (pin "2") (pinfunction "2_2") (pintype "bidirectional"))
      (node (ref "R7") (pin "2") (pinfunction "2_2") (pintype "passive"))
      (node (ref "R8") (pin "1") (pinfunction "1_1") (pintype "passive"))
    )
    (net (code "22") (name "Net-(B2-Pad1)") (class "Default")
      (node (ref "B2") (pin "1") (pinfunction "1_1") (pintype "bidirectional"))
      (node (ref "B2") (pin "2") (pinfunction "2_2") (pintype "bidirectional"))
      (node (ref "R10") (pin "1") (pinfunction "1_1") (pintype "passive"))
      (node (ref "R11") (pin "2") (pinfunction "2_2") (pintype "passive"))
    )
    (net (code "23") (name "Net-(B3-Pad1)") (class "Default")
      (node (ref "B3") (pin "1") (pinfunction "1_1") (pintype "bidirectional"))
      (node (ref "B3") (pin "2") (pinfunction "2_2") (pintype "bidirectional"))
      (node (ref "R13") (pin "1") (pinfunction "1_1") (pintype "passive"))
      (node (ref "R14") (pin "1") (pinfunction "1_1") (pintype "passive"))
    )
    (net (code "24") (name "Net-(B4-Pad3)") (class "Default")
      (node (ref "B4") (pin "3") (pinfunction "3_3") (pintype "bidirectional"))
      (node (ref "B4") (pin "4") (pinfunction "4_4") (pintype "bidirectional"))
      (node (ref "R12") (pin "1") (pinfunction "1_1") (pintype "passive"))
      (node (ref "R9") (pin "1") (pinfunction "1_1") (pintype "passive"))
    )
    (net (code "25") (name "Net-(D1-CBLUE)") (class "Default")
      (node (ref "D1") (pin "C_BLUE") (pinfunction "CBLUE_C_BLUE") (pintype "passive"))
      (node (ref "U1") (pin "P7") (pinfunction "LED1_P7") (pintype "bidirectional"))
    )
    (net (code "26") (name "Net-(D1-CGREEN)") (class "Default")
      (node (ref "D1") (pin "C_GREEN") (pinfunction "CGREEN_C_GREEN") (pintype "passive"))
      (node (ref "U1") (pin "P8") (pinfunction "LED2_P8") (pintype "bidirectional"))
    )
    (net (code "27") (name "Net-(D1-CRED)") (class "Default")
      (node (ref "D1") (pin "C_RED") (pinfunction "CRED_C_RED") (pintype "passive"))
      (node (ref "U1") (pin "P6") (pinfunction "LED0_P6") (pintype "bidirectional"))
    )
    (net (code "28") (name "Net-(D2-CBLUE)") (class "Default")
      (node (ref "D2") (pin "C_BLUE") (pinfunction "CBLUE_C_BLUE") (pintype "passive"))
      (node (ref "U1") (pin "P11") (pinfunction "LED4_P11") (pintype "bidirectional"))
    )
    (net (code "29") (name "Net-(D2-CGREEN)") (class "Default")
      (node (ref "D2") (pin "C_GREEN") (pinfunction "CGREEN_C_GREEN") (pintype "passive"))
      (node (ref "U1") (pin "P12") (pinfunction "LED5_P12") (pintype "bidirectional"))
    )
    (net (code "30") (name "Net-(D2-CRED)") (class "Default")
      (node (ref "D2") (pin "C_RED") (pinfunction "CRED_C_RED") (pintype "passive"))
      (node (ref "U1") (pin "P9") (pinfunction "LED3_P9") (pintype "bidirectional"))
    )
    (net (code "31") (name "Net-(D3-CBLUE)") (class "Default")
      (node (ref "D3") (pin "C_BLUE") (pinfunction "CBLUE_C_BLUE") (pintype "passive"))
      (node (ref "U1") (pin "P14") (pinfunction "LED7_P14") (pintype "bidirectional"))
    )
    (net (code "32") (name "Net-(D3-CGREEN)") (class "Default")
      (node (ref "D3") (pin "C_GREEN") (pinfunction "CGREEN_C_GREEN") (pintype "passive"))
      (node (ref "U1") (pin "P15") (pinfunction "LED8_P15") (pintype "bidirectional"))
    )
    (net (code "33") (name "Net-(D3-CRED)") (class "Default")
      (node (ref "D3") (pin "C_RED") (pinfunction "CRED_C_RED") (pintype "passive"))
      (node (ref "U1") (pin "P13") (pinfunction "LED6_P13") (pintype "bidirectional"))
    )
    (net (code "34") (name "Net-(D4-CBLUE)") (class "Default")
      (node (ref "D4") (pin "C_BLUE") (pinfunction "CBLUE_C_BLUE") (pintype "passive"))
      (node (ref "U1") (pin "P17") (pinfunction "LED10_P17") (pintype "bidirectional"))
    )
    (net (code "35") (name "Net-(D4-CGREEN)") (class "Default")
      (node (ref "D4") (pin "C_GREEN") (pinfunction "CGREEN_C_GREEN") (pintype "passive"))
      (node (ref "U1") (pin "P18") (pinfunction "LED11_P18") (pintype "bidirectional"))
    )
    (net (code "36") (name "Net-(D4-CRED)") (class "Default")
      (node (ref "D4") (pin "C_RED") (pinfunction "CRED_C_RED") (pintype "passive"))
      (node (ref "U1") (pin "P16") (pinfunction "LED9_P16") (pintype "bidirectional"))
    )
    (net (code "37") (name "Net-(D5-CBLUE)") (class "Default")
      (node (ref "D5") (pin "C_BLUE") (pinfunction "CBLUE_C_BLUE") (pintype "passive"))
      (node (ref "U1") (pin "P21") (pinfunction "LED13_P21") (pintype "bidirectional"))
    )
    (net (code "38") (name "Net-(D5-CGREEN)") (class "Default")
      (node (ref "D5") (pin "C_GREEN") (pinfunction "CGREEN_C_GREEN") (pintype "passive"))
      (node (ref "U1") (pin "P22") (pinfunction "LED14_P22") (pintype "bidirectional"))
    )
    (net (code "39") (name "Net-(D5-CRED)") (class "Default")
      (node (ref "D5") (pin "C_RED") (pinfunction "CRED_C_RED") (pintype "passive"))
      (node (ref "U1") (pin "P20") (pinfunction "LED12_P20") (pintype "bidirectional"))
    )
    (net (code "40") (name "Net-(D6-CBLUE)") (class "Default")
      (node (ref "D6") (pin "C_BLUE") (pinfunction "CBLUE_C_BLUE") (pintype "passive"))
      (node (ref "U2") (pin "P7") (pinfunction "LED1_P7") (pintype "bidirectional"))
    )
    (net (code "41") (name "Net-(D6-CGREEN)") (class "Default")
      (node (ref "D6") (pin "C_GREEN") (pinfunction "CGREEN_C_GREEN") (pintype "passive"))
      (node (ref "U2") (pin "P8") (pinfunction "LED2_P8") (pintype "bidirectional"))
    )
    (net (code "42") (name "Net-(D6-CRED)") (class "Default")
      (node (ref "D6") (pin "C_RED") (pinfunction "CRED_C_RED") (pintype "passive"))
      (node (ref "U2") (pin "P6") (pinfunction "LED0_P6") (pintype "bidirectional"))
    )
    (net (code "43") (name "Net-(D7-CBLUE)") (class "Default")
      (node (ref "D7") (pin "C_BLUE") (pinfunction "CBLUE_C_BLUE") (pintype "passive"))
      (node (ref "U2") (pin "P11") (pinfunction "LED4_P11") (pintype "bidirectional"))
    )
    (net (code "44") (name "Net-(D7-CGREEN)") (class "Default")
      (node (ref "D7") (pin "C_GREEN") (pinfunction "CGREEN_C_GREEN") (pintype "passive"))
      (node (ref "U2") (pin "P12") (pinfunction "LED5_P12") (pintype "bidirectional"))
    )
    (net (code "45") (name "Net-(D7-CRED)") (class "Default")
      (node (ref "D7") (pin "C_RED") (pinfunction "CRED_C_RED") (pintype "passive"))
      (node (ref "U2") (pin "P9") (pinfunction "LED3_P9") (pintype "bidirectional"))
    )
    (net (code "46") (name "Net-(D8-CBLUE)") (class "Default")
      (node (ref "D8") (pin "C_BLUE") (pinfunction "CBLUE_C_BLUE") (pintype "passive"))
      (node (ref "U2") (pin "P14") (pinfunction "LED7_P14") (pintype "bidirectional"))
    )
    (net (code "47") (name "Net-(D8-CGREEN)") (class "Default")
      (node (ref "D8") (pin "C_GREEN") (pinfunction "CGREEN_C_GREEN") (pintype "passive"))
      (node (ref "U2") (pin "P15") (pinfunction "LED8_P15") (pintype "bidirectional"))
    )
    (net (code "48") (name "Net-(D8-CRED)") (class "Default")
      (node (ref "D8") (pin "C_RED") (pinfunction "CRED_C_RED") (pintype "passive"))
      (node (ref "U2") (pin "P13") (pinfunction "LED6_P13") (pintype "bidirectional"))
    )
    (net (code "49") (name "Net-(D9-CBLUE)") (class "Default")
      (node (ref "D9") (pin "C_BLUE") (pinfunction "CBLUE_C_BLUE") (pintype "passive"))
      (node (ref "U2") (pin "P17") (pinfunction "LED10_P17") (pintype "bidirectional"))
    )
    (net (code "50") (name "Net-(D9-CGREEN)") (class "Default")
      (node (ref "D9") (pin "C_GREEN") (pinfunction "CGREEN_C_GREEN") (pintype "passive"))
      (node (ref "U2") (pin "P18") (pinfunction "LED11_P18") (pintype "bidirectional"))
    )
    (net (code "51") (name "Net-(D9-CRED)") (class "Default")
      (node (ref "D9") (pin "C_RED") (pinfunction "CRED_C_RED") (pintype "passive"))
      (node (ref "U2") (pin "P16") (pinfunction "LED9_P16") (pintype "bidirectional"))
    )
    (net (code "52") (name "Net-(U$1A-PA15)") (class "Default")
      (node (ref "R3") (pin "1") (pinfunction "1_1") (pintype "passive"))
      (node (ref "TP8") (pin "TP") (pinfunction "TP_TP") (pintype "input"))
      (node (ref "U$1") (pin "25") (pinfunction "PA15_25") (pintype "bidirectional"))
      (node (ref "U1") (pin "P26") (pinfunction "SCL_P26") (pintype "input"))
      (node (ref "U2") (pin "P26") (pinfunction "SCL_P26") (pintype "input"))
    )
    (net (code "53") (name "Net-(U$1B-PB7)") (class "Default")
      (node (ref "R4") (pin "1") (pinfunction "1_1") (pintype "passive"))
      (node (ref "TP9") (pin "TP") (pinfunction "TP_TP") (pintype "input"))
      (node (ref "U$1") (pin "30") (pinfunction "PB7_30") (pintype "bidirectional"))
      (node (ref "U1") (pin "P27") (pinfunction "SDA_P27") (pintype "input"))
      (node (ref "U2") (pin "P27") (pinfunction "SDA_P27") (pintype "input"))
    )
    (net (code "54") (name "Net-(U$1C-PG10{slash}~{NRST})") (class "Default")
      (node (ref "TP35") (pin "TP") (pinfunction "TP_TP") (pintype "input"))
      (node (ref "U$1") (pin "4") (pinfunction "PG10/~{NRST}_4") (pintype "bidirectional"))
    )
    (net (code "55") (name "Net-(U1-REXT)") (class "Default")
      (node (ref "R1") (pin "2") (pinfunction "2_2") (pintype "passive"))
      (node (ref "U1") (pin "P1") (pinfunction "REXT_P1") (pintype "bidirectional"))
    )
    (net (code "56") (name "Net-(U2-REXT)") (class "Default")
      (node (ref "R2") (pin "2") (pinfunction "2_2") (pintype "passive"))
      (node (ref "U2") (pin "P1") (pinfunction "REXT_P1") (pintype "bidirectional"))
    )
    (net (code "57") (name "unconnected-(U$1A-PA8-Pad18)") (class "Default")
      (node (ref "U$1") (pin "18") (pinfunction "PA8_18") (pintype "bidirectional"))
    )
    (net (code "58") (name "unconnected-(U$1A-PA11-Pad21)") (class "Default")
      (node (ref "U$1") (pin "21") (pinfunction "PA11_21") (pintype "bidirectional"))
    )
    (net (code "59") (name "unconnected-(U$1B-PB3-Pad26)") (class "Default")
      (node (ref "U$1") (pin "26") (pinfunction "PB3_26") (pintype "bidirectional"))
    )
    (net (code "60") (name "unconnected-(U$1B-PB5-Pad28)") (class "Default")
      (node (ref "U$1") (pin "28") (pinfunction "PB5_28") (pintype "bidirectional"))
    )
    (net (code "61") (name "unconnected-(U$1C-PB8{slash}BOOT0-Pad31)") (class "Default")
      (node (ref "U$1") (pin "31") (pinfunction "PB8/BOOT0_31") (pintype "input"))
    )
    (net (code "62") (name "unconnected-(U$1C-PF1{slash}OSC_OUT-Pad3)") (class "Default")
      (node (ref "U$1") (pin "3") (pinfunction "PF1/OSC_OUT_3") (pintype "input"))
    )
    (net (code "63") (name "unconnected-(U1-LED15-PadP23)") (class "Default")
      (node (ref "U1") (pin "P23") (pinfunction "LED15_P23") (pintype "bidirectional"))
    )
    (net (code "64") (name "unconnected-(U2-LED12-PadP20)") (class "Default")
      (node (ref "U2") (pin "P20") (pinfunction "LED12_P20") (pintype "bidirectional"))
    )
    (net (code "65") (name "unconnected-(U2-LED13-PadP21)") (class "Default")
      (node (ref "U2") (pin "P21") (pinfunction "LED13_P21") (pintype "bidirectional"))
    )
    (net (code "66") (name "unconnected-(U2-LED14-PadP22)") (class "Default")
      (node (ref "U2") (pin "P22") (pinfunction "LED14_P22") (pintype "bidirectional"))
    )
    (net (code "67") (name "unconnected-(U2-LED15-PadP23)") (class "Default")
      (node (ref "U2") (pin "P23") (pinfunction "LED15_P23") (pintype "bidirectional"))
    )
  )
)
